# Button_Board.net
KiCad netlist of a schematic drawn in EAGLE
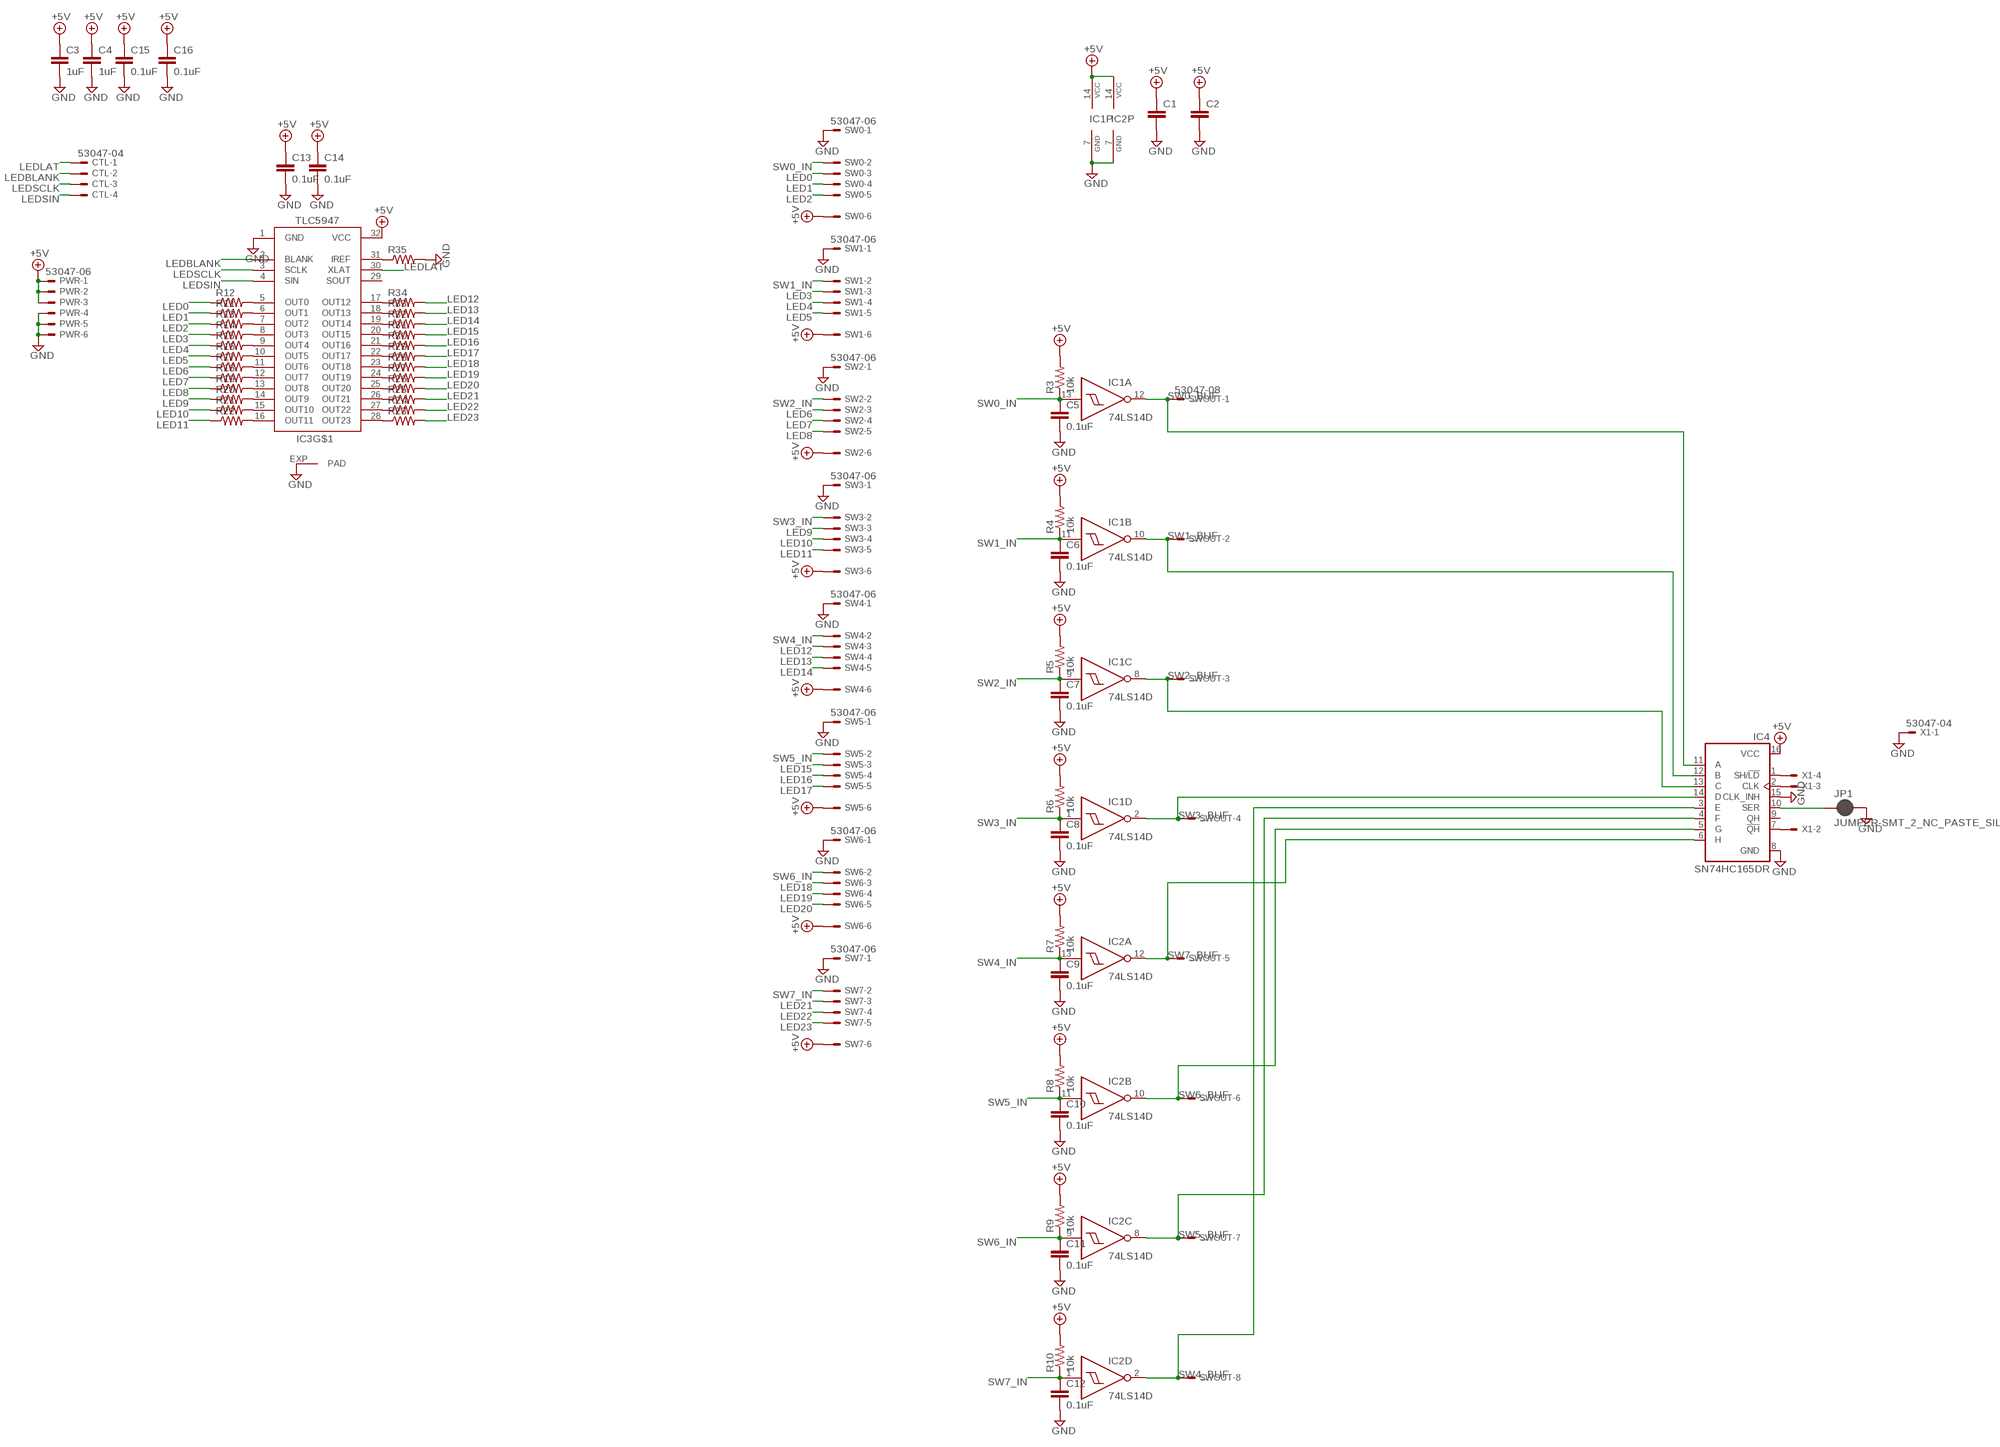
[diagram p0: schematic, sheet 1]

(export (version "E")
  (design (tool "Eeschema 10.0.6"))
  (components
    (comp (ref "C1")
      (value "C-EUC1206")
      (footprint "eagle-import:C1206")
      (libsource (lib "eagle-import") (part "C-EUC1206"))
    )
    (comp (ref "C2")
      (value "C-EUC1206")
      (footprint "eagle-import:C1206")
      (libsource (lib "eagle-import") (part "C-EUC1206"))
    )
    (comp (ref "C3")
      (value "1uF")
      (footprint "eagle-import:C1206K")
      (libsource (lib "eagle-import") (part "C-EUC1206K"))
    )
    (comp (ref "C4")
      (value "1uF")
      (footprint "eagle-import:C1206K")
      (libsource (lib "eagle-import") (part "C-EUC1206K"))
    )
    (comp (ref "C5")
      (value "0.1uF")
      (footprint "eagle-import:C1206")
      (libsource (lib "eagle-import") (part "C-EUC1206"))
    )
    (comp (ref "C6")
      (value "0.1uF")
      (footprint "eagle-import:C1206")
      (libsource (lib "eagle-import") (part "C-EUC1206"))
    )
    (comp (ref "C7")
      (value "0.1uF")
      (footprint "eagle-import:C1206")
      (libsource (lib "eagle-import") (part "C-EUC1206"))
    )
    (comp (ref "C8")
      (value "0.1uF")
      (footprint "eagle-import:C1206")
      (libsource (lib "eagle-import") (part "C-EUC1206"))
    )
    (comp (ref "C9")
      (value "0.1uF")
      (footprint "eagle-import:C1206")
      (libsource (lib "eagle-import") (part "C-EUC1206"))
    )
    (comp (ref "C10")
      (value "0.1uF")
      (footprint "eagle-import:C1206")
      (libsource (lib "eagle-import") (part "C-EUC1206"))
    )
    (comp (ref "C11")
      (value "0.1uF")
      (footprint "eagle-import:C1206")
      (libsource (lib "eagle-import") (part "C-EUC1206"))
    )
    (comp (ref "C12")
      (value "0.1uF")
      (footprint "eagle-import:C1206")
      (libsource (lib "eagle-import") (part "C-EUC1206"))
    )
    (comp (ref "C13")
      (value "0.1uF")
      (footprint "eagle-import:C1206")
      (libsource (lib "eagle-import") (part "C-EUC1206"))
    )
    (comp (ref "C14")
      (value "0.1uF")
      (footprint "eagle-import:C1206")
      (libsource (lib "eagle-import") (part "C-EUC1206"))
    )
    (comp (ref "C15")
      (value "0.1uF")
      (footprint "eagle-import:C1206K")
      (libsource (lib "eagle-import") (part "C-EUC1206K"))
    )
    (comp (ref "C16")
      (value "0.1uF")
      (footprint "eagle-import:C1206K")
      (libsource (lib "eagle-import") (part "C-EUC1206K"))
    )
    (comp (ref "CTL")
      (value "53047-04")
      (footprint "eagle-import:53047-04")
      (fields (field (name "MF") "WALDOM/MOLEX") (field (name "MPN") "53047-0410"))
      (libsource (lib "eagle-import") (part "53?-04047"))
    )
    (comp (ref "IC1")
      (value "74LS14D")
      (footprint "eagle-import:SO14")
      (libsource (lib "eagle-import") (part "7414DLS"))
    )
    (comp (ref "IC2")
      (value "74LS14D")
      (footprint "eagle-import:SO14")
      (libsource (lib "eagle-import") (part "7414DLS"))
    )
    (comp (ref "IC3")
      (value "TLC5947-DAP")
      (footprint "eagle-import:HTSSOP32DAP")
      (libsource (lib "eagle-import") (part "TLC5947-DAP"))
    )
    (comp (ref "IC4")
      (value "SN74HC165DR")
      (footprint "eagle-import:SO16")
      (libsource (lib "eagle-import") (part "74165DHC"))
    )
    (comp (ref "JP1")
      (value "JUMPER-SMT_2_NC_PASTE_SILK")
      (footprint "eagle-import:SMT-JUMPER_2_NC_PASTE_SILK")
      (libsource (lib "eagle-import") (part "JUMPER-SMT_2_NC_PASTE_SILK"))
    )
    (comp (ref "PWR")
      (value "53047-06")
      (footprint "eagle-import:53047-06")
      (fields (field (name "MPN") "53047-0610-C"))
      (libsource (lib "eagle-import") (part "53?-06047"))
    )
    (comp (ref "R3")
      (value "10k")
      (footprint "eagle-import:M1206")
      (libsource (lib "eagle-import") (part "R-US_M1206"))
    )
    (comp (ref "R4")
      (value "10k")
      (footprint "eagle-import:M1206")
      (libsource (lib "eagle-import") (part "R-US_M1206"))
    )
    (comp (ref "R5")
      (value "10k")
      (footprint "eagle-import:M1206")
      (libsource (lib "eagle-import") (part "R-US_M1206"))
    )
    (comp (ref "R6")
      (value "10k")
      (footprint "eagle-import:M1206")
      (libsource (lib "eagle-import") (part "R-US_M1206"))
    )
    (comp (ref "R7")
      (value "10k")
      (footprint "eagle-import:M1206")
      (libsource (lib "eagle-import") (part "R-US_M1206"))
    )
    (comp (ref "R8")
      (value "10k")
      (footprint "eagle-import:M1206")
      (libsource (lib "eagle-import") (part "R-US_M1206"))
    )
    (comp (ref "R9")
      (value "10k")
      (footprint "eagle-import:M1206")
      (libsource (lib "eagle-import") (part "R-US_M1206"))
    )
    (comp (ref "R10")
      (value "10k")
      (footprint "eagle-import:M1206")
      (libsource (lib "eagle-import") (part "R-US_M1206"))
    )
    (comp (ref "R11")
      (value "R-US_M1206")
      (footprint "eagle-import:M1206")
      (libsource (lib "eagle-import") (part "R-US_M1206"))
    )
    (comp (ref "R12")
      (value "R-US_M1206")
      (footprint "eagle-import:M1206")
      (libsource (lib "eagle-import") (part "R-US_M1206"))
    )
    (comp (ref "R13")
      (value "R-US_M1206")
      (footprint "eagle-import:M1206")
      (libsource (lib "eagle-import") (part "R-US_M1206"))
    )
    (comp (ref "R14")
      (value "R-US_M1206")
      (footprint "eagle-import:M1206")
      (libsource (lib "eagle-import") (part "R-US_M1206"))
    )
    (comp (ref "R15")
      (value "R-US_M1206")
      (footprint "eagle-import:M1206")
      (libsource (lib "eagle-import") (part "R-US_M1206"))
    )
    (comp (ref "R16")
      (value "R-US_M1206")
      (footprint "eagle-import:M1206")
      (libsource (lib "eagle-import") (part "R-US_M1206"))
    )
    (comp (ref "R17")
      (value "R-US_M1206")
      (footprint "eagle-import:M1206")
      (libsource (lib "eagle-import") (part "R-US_M1206"))
    )
    (comp (ref "R18")
      (value "R-US_M1206")
      (footprint "eagle-import:M1206")
      (libsource (lib "eagle-import") (part "R-US_M1206"))
    )
    (comp (ref "R19")
      (value "R-US_M1206")
      (footprint "eagle-import:M1206")
      (libsource (lib "eagle-import") (part "R-US_M1206"))
    )
    (comp (ref "R20")
      (value "R-US_M1206")
      (footprint "eagle-import:M1206")
      (libsource (lib "eagle-import") (part "R-US_M1206"))
    )
    (comp (ref "R21")
      (value "R-US_M1206")
      (footprint "eagle-import:M1206")
      (libsource (lib "eagle-import") (part "R-US_M1206"))
    )
    (comp (ref "R22")
      (value "R-US_M1206")
      (footprint "eagle-import:M1206")
      (libsource (lib "eagle-import") (part "R-US_M1206"))
    )
    (comp (ref "R23")
      (value "R-US_M1206")
      (footprint "eagle-import:M1206")
      (libsource (lib "eagle-import") (part "R-US_M1206"))
    )
    (comp (ref "R24")
      (value "R-US_M1206")
      (footprint "eagle-import:M1206")
      (libsource (lib "eagle-import") (part "R-US_M1206"))
    )
    (comp (ref "R25")
      (value "R-US_M1206")
      (footprint "eagle-import:M1206")
      (libsource (lib "eagle-import") (part "R-US_M1206"))
    )
    (comp (ref "R26")
      (value "R-US_M1206")
      (footprint "eagle-import:M1206")
      (libsource (lib "eagle-import") (part "R-US_M1206"))
    )
    (comp (ref "R27")
      (value "R-US_M1206")
      (footprint "eagle-import:M1206")
      (libsource (lib "eagle-import") (part "R-US_M1206"))
    )
    (comp (ref "R28")
      (value "R-US_M1206")
      (footprint "eagle-import:M1206")
      (libsource (lib "eagle-import") (part "R-US_M1206"))
    )
    (comp (ref "R29")
      (value "R-US_M1206")
      (footprint "eagle-import:M1206")
      (libsource (lib "eagle-import") (part "R-US_M1206"))
    )
    (comp (ref "R30")
      (value "R-US_M1206")
      (footprint "eagle-import:M1206")
      (libsource (lib "eagle-import") (part "R-US_M1206"))
    )
    (comp (ref "R31")
      (value "R-US_M1206")
      (footprint "eagle-import:M1206")
      (libsource (lib "eagle-import") (part "R-US_M1206"))
    )
    (comp (ref "R32")
      (value "R-US_M1206")
      (footprint "eagle-import:M1206")
      (libsource (lib "eagle-import") (part "R-US_M1206"))
    )
    (comp (ref "R33")
      (value "R-US_M1206")
      (footprint "eagle-import:M1206")
      (libsource (lib "eagle-import") (part "R-US_M1206"))
    )
    (comp (ref "R34")
      (value "R-US_M1206")
      (footprint "eagle-import:M1206")
      (libsource (lib "eagle-import") (part "R-US_M1206"))
    )
    (comp (ref "R35")
      (value "R-US_M1206")
      (footprint "eagle-import:M1206")
      (libsource (lib "eagle-import") (part "R-US_M1206"))
    )
    (comp (ref "SW0")
      (value "53047-06")
      (footprint "eagle-import:53047-06")
      (fields (field (name "MPN") "53047-0610-C"))
      (libsource (lib "eagle-import") (part "53?-06047"))
    )
    (comp (ref "SW1")
      (value "53047-06")
      (footprint "eagle-import:53047-06")
      (fields (field (name "MPN") "53047-0610-C"))
      (libsource (lib "eagle-import") (part "53?-06047"))
    )
    (comp (ref "SW2")
      (value "53047-06")
      (footprint "eagle-import:53047-06")
      (fields (field (name "MPN") "53047-0610-C"))
      (libsource (lib "eagle-import") (part "53?-06047"))
    )
    (comp (ref "SW3")
      (value "53047-06")
      (footprint "eagle-import:53047-06")
      (fields (field (name "MPN") "53047-0610-C"))
      (libsource (lib "eagle-import") (part "53?-06047"))
    )
    (comp (ref "SW4")
      (value "53047-06")
      (footprint "eagle-import:53047-06")
      (fields (field (name "MPN") "53047-0610-C"))
      (libsource (lib "eagle-import") (part "53?-06047"))
    )
    (comp (ref "SW5")
      (value "53047-06")
      (footprint "eagle-import:53047-06")
      (fields (field (name "MPN") "53047-0610-C"))
      (libsource (lib "eagle-import") (part "53?-06047"))
    )
    (comp (ref "SW6")
      (value "53047-06")
      (footprint "eagle-import:53047-06")
      (fields (field (name "MPN") "53047-0610-C"))
      (libsource (lib "eagle-import") (part "53?-06047"))
    )
    (comp (ref "SW7")
      (value "53047-06")
      (footprint "eagle-import:53047-06")
      (fields (field (name "MPN") "53047-0610-C"))
      (libsource (lib "eagle-import") (part "53?-06047"))
    )
    (comp (ref "SWOUT")
      (value "53047-08")
      (footprint "eagle-import:53047-08")
      (fields (field (name "MPN") "53047-0810"))
      (libsource (lib "eagle-import") (part "53?-08047"))
    )
    (comp (ref "X1")
      (value "53047-04")
      (footprint "eagle-import:53047-04")
      (fields (field (name "MF") "WALDOM/MOLEX") (field (name "MPN") "53047-0410"))
      (libsource (lib "eagle-import") (part "53?-04047"))
    )
  )
  (nets
    (net (code "1") (name "+5V") (class "Default")
      (node (ref "C1") (pin "1") (pinfunction "1_1") (pintype "passive"))
      (node (ref "C13") (pin "1") (pinfunction "1_1") (pintype "passive"))
      (node (ref "C14") (pin "1") (pinfunction "1_1") (pintype "passive"))
      (node (ref "C15") (pin "1") (pinfunction "1_1") (pintype "passive"))
      (node (ref "C16") (pin "1") (pinfunction "1_1") (pintype "passive"))
      (node (ref "C2") (pin "1") (pinfunction "1_1") (pintype "passive"))
      (node (ref "C3") (pin "1") (pinfunction "1_1") (pintype "passive"))
      (node (ref "C4") (pin "1") (pinfunction "1_1") (pintype "passive"))
      (node (ref "IC1") (pin "14") (pinfunction "VCC_14") (pintype "power_in"))
      (node (ref "IC2") (pin "14") (pinfunction "VCC_14") (pintype "power_in"))
      (node (ref "IC3") (pin "32") (pinfunction "VCC_32") (pintype "power_in"))
      (node (ref "IC4") (pin "16") (pinfunction "VCC_16") (pintype "power_in"))
      (node (ref "PWR") (pin "1") (pinfunction "S_1") (pintype "passive"))
      (node (ref "PWR") (pin "2") (pinfunction "S_2") (pintype "passive"))
      (node (ref "PWR") (pin "3") (pinfunction "S_3") (pintype "passive"))
      (node (ref "R10") (pin "2") (pinfunction "2_2") (pintype "passive"))
      (node (ref "R3") (pin "2") (pinfunction "2_2") (pintype "passive"))
      (node (ref "R4") (pin "2") (pinfunction "2_2") (pintype "passive"))
      (node (ref "R5") (pin "2") (pinfunction "2_2") (pintype "passive"))
      (node (ref "R6") (pin "2") (pinfunction "2_2") (pintype "passive"))
      (node (ref "R7") (pin "2") (pinfunction "2_2") (pintype "passive"))
      (node (ref "R8") (pin "2") (pinfunction "2_2") (pintype "passive"))
      (node (ref "R9") (pin "2") (pinfunction "2_2") (pintype "passive"))
      (node (ref "SW0") (pin "6") (pinfunction "S_6") (pintype "passive"))
      (node (ref "SW1") (pin "6") (pinfunction "S_6") (pintype "passive"))
      (node (ref "SW2") (pin "6") (pinfunction "S_6") (pintype "passive"))
      (node (ref "SW3") (pin "6") (pinfunction "S_6") (pintype "passive"))
      (node (ref "SW4") (pin "6") (pinfunction "S_6") (pintype "passive"))
      (node (ref "SW5") (pin "6") (pinfunction "S_6") (pintype "passive"))
      (node (ref "SW6") (pin "6") (pinfunction "S_6") (pintype "passive"))
      (node (ref "SW7") (pin "6") (pinfunction "S_6") (pintype "passive"))
    )
    (net (code "2") (name "/LED0") (class "Default")
      (node (ref "R12") (pin "1") (pinfunction "1_1") (pintype "passive"))
      (node (ref "SW0") (pin "3") (pinfunction "S_3") (pintype "passive"))
    )
    (net (code "3") (name "/LED1") (class "Default")
      (node (ref "R11") (pin "1") (pinfunction "1_1") (pintype "passive"))
      (node (ref "SW0") (pin "4") (pinfunction "S_4") (pintype "passive"))
    )
    (net (code "4") (name "/LED2") (class "Default")
      (node (ref "R13") (pin "1") (pinfunction "1_1") (pintype "passive"))
      (node (ref "SW0") (pin "5") (pinfunction "S_5") (pintype "passive"))
    )
    (net (code "5") (name "/LED3") (class "Default")
      (node (ref "R14") (pin "1") (pinfunction "1_1") (pintype "passive"))
      (node (ref "SW1") (pin "3") (pinfunction "S_3") (pintype "passive"))
    )
    (net (code "6") (name "/LED4") (class "Default")
      (node (ref "R15") (pin "1") (pinfunction "1_1") (pintype "passive"))
      (node (ref "SW1") (pin "4") (pinfunction "S_4") (pintype "passive"))
    )
    (net (code "7") (name "/LED5") (class "Default")
      (node (ref "R16") (pin "1") (pinfunction "1_1") (pintype "passive"))
      (node (ref "SW1") (pin "5") (pinfunction "S_5") (pintype "passive"))
    )
    (net (code "8") (name "/LED6") (class "Default")
      (node (ref "R17") (pin "1") (pinfunction "1_1") (pintype "passive"))
      (node (ref "SW2") (pin "3") (pinfunction "S_3") (pintype "passive"))
    )
    (net (code "9") (name "/LED7") (class "Default")
      (node (ref "R18") (pin "1") (pinfunction "1_1") (pintype "passive"))
      (node (ref "SW2") (pin "4") (pinfunction "S_4") (pintype "passive"))
    )
    (net (code "10") (name "/LED8") (class "Default")
      (node (ref "R19") (pin "1") (pinfunction "1_1") (pintype "passive"))
      (node (ref "SW2") (pin "5") (pinfunction "S_5") (pintype "passive"))
    )
    (net (code "11") (name "/LED9") (class "Default")
      (node (ref "R20") (pin "1") (pinfunction "1_1") (pintype "passive"))
      (node (ref "SW3") (pin "3") (pinfunction "S_3") (pintype "passive"))
    )
    (net (code "12") (name "/LED10") (class "Default")
      (node (ref "R21") (pin "1") (pinfunction "1_1") (pintype "passive"))
      (node (ref "SW3") (pin "4") (pinfunction "S_4") (pintype "passive"))
    )
    (net (code "13") (name "/LED11") (class "Default")
      (node (ref "R22") (pin "1") (pinfunction "1_1") (pintype "passive"))
      (node (ref "SW3") (pin "5") (pinfunction "S_5") (pintype "passive"))
    )
    (net (code "14") (name "/LED12") (class "Default")
      (node (ref "R34") (pin "2") (pinfunction "2_2") (pintype "passive"))
      (node (ref "SW4") (pin "3") (pinfunction "S_3") (pintype "passive"))
    )
    (net (code "15") (name "/LED13") (class "Default")
      (node (ref "R33") (pin "2") (pinfunction "2_2") (pintype "passive"))
      (node (ref "SW4") (pin "4") (pinfunction "S_4") (pintype "passive"))
    )
    (net (code "16") (name "/LED14") (class "Default")
      (node (ref "R32") (pin "2") (pinfunction "2_2") (pintype "passive"))
      (node (ref "SW4") (pin "5") (pinfunction "S_5") (pintype "passive"))
    )
    (net (code "17") (name "/LED15") (class "Default")
      (node (ref "R31") (pin "2") (pinfunction "2_2") (pintype "passive"))
      (node (ref "SW5") (pin "3") (pinfunction "S_3") (pintype "passive"))
    )
    (net (code "18") (name "/LED16") (class "Default")
      (node (ref "R30") (pin "2") (pinfunction "2_2") (pintype "passive"))
      (node (ref "SW5") (pin "4") (pinfunction "S_4") (pintype "passive"))
    )
    (net (code "19") (name "/LED17") (class "Default")
      (node (ref "R29") (pin "2") (pinfunction "2_2") (pintype "passive"))
      (node (ref "SW5") (pin "5") (pinfunction "S_5") (pintype "passive"))
    )
    (net (code "20") (name "/LED18") (class "Default")
      (node (ref "R28") (pin "2") (pinfunction "2_2") (pintype "passive"))
      (node (ref "SW6") (pin "3") (pinfunction "S_3") (pintype "passive"))
    )
    (net (code "21") (name "/LED19") (class "Default")
      (node (ref "R27") (pin "2") (pinfunction "2_2") (pintype "passive"))
      (node (ref "SW6") (pin "4") (pinfunction "S_4") (pintype "passive"))
    )
    (net (code "22") (name "/LED20") (class "Default")
      (node (ref "R26") (pin "2") (pinfunction "2_2") (pintype "passive"))
      (node (ref "SW6") (pin "5") (pinfunction "S_5") (pintype "passive"))
    )
    (net (code "23") (name "/LED21") (class "Default")
      (node (ref "R25") (pin "2") (pinfunction "2_2") (pintype "passive"))
      (node (ref "SW7") (pin "3") (pinfunction "S_3") (pintype "passive"))
    )
    (net (code "24") (name "/LED22") (class "Default")
      (node (ref "R24") (pin "2") (pinfunction "2_2") (pintype "passive"))
      (node (ref "SW7") (pin "4") (pinfunction "S_4") (pintype "passive"))
    )
    (net (code "25") (name "/LED23") (class "Default")
      (node (ref "R23") (pin "2") (pinfunction "2_2") (pintype "passive"))
      (node (ref "SW7") (pin "5") (pinfunction "S_5") (pintype "passive"))
    )
    (net (code "26") (name "/LEDBLANK") (class "Default")
      (node (ref "CTL") (pin "2") (pinfunction "S_2") (pintype "passive"))
      (node (ref "IC3") (pin "2") (pinfunction "BLANK_2") (pintype "input"))
    )
    (net (code "27") (name "/LEDLAT") (class "Default")
      (node (ref "CTL") (pin "1") (pinfunction "S_1") (pintype "passive"))
      (node (ref "IC3") (pin "30") (pinfunction "XLAT_30") (pintype "input"))
    )
    (net (code "28") (name "/LEDSCLK") (class "Default")
      (node (ref "CTL") (pin "3") (pinfunction "S_3") (pintype "passive"))
      (node (ref "IC3") (pin "3") (pinfunction "SCLK_3") (pintype "input"))
    )
    (net (code "29") (name "/LEDSIN") (class "Default")
      (node (ref "CTL") (pin "4") (pinfunction "S_4") (pintype "passive"))
      (node (ref "IC3") (pin "4") (pinfunction "SIN_4") (pintype "input"))
    )
    (net (code "30") (name "/SW0_BUF") (class "Default")
      (node (ref "IC1") (pin "12") (pinfunction "O_12") (pintype "output"))
      (node (ref "IC4") (pin "11") (pinfunction "A_11") (pintype "tri_state"))
      (node (ref "SWOUT") (pin "1") (pinfunction "S_1") (pintype "passive"))
    )
    (net (code "31") (name "/SW0_IN") (class "Default")
      (node (ref "C5") (pin "1") (pinfunction "1_1") (pintype "passive"))
      (node (ref "IC1") (pin "13") (pinfunction "I_13") (pintype "input"))
      (node (ref "R3") (pin "1") (pinfunction "1_1") (pintype "passive"))
      (node (ref "SW0") (pin "2") (pinfunction "S_2") (pintype "passive"))
    )
    (net (code "32") (name "/SW1_BUF") (class "Default")
      (node (ref "IC1") (pin "10") (pinfunction "O_10") (pintype "output"))
      (node (ref "IC4") (pin "12") (pinfunction "B_12") (pintype "tri_state"))
      (node (ref "SWOUT") (pin "2") (pinfunction "S_2") (pintype "passive"))
    )
    (net (code "33") (name "/SW1_IN") (class "Default")
      (node (ref "C6") (pin "1") (pinfunction "1_1") (pintype "passive"))
      (node (ref "IC1") (pin "11") (pinfunction "I_11") (pintype "input"))
      (node (ref "R4") (pin "1") (pinfunction "1_1") (pintype "passive"))
      (node (ref "SW1") (pin "2") (pinfunction "S_2") (pintype "passive"))
    )
    (net (code "34") (name "/SW2_BUF") (class "Default")
      (node (ref "IC1") (pin "8") (pinfunction "O_8") (pintype "output"))
      (node (ref "IC4") (pin "13") (pinfunction "C_13") (pintype "tri_state"))
      (node (ref "SWOUT") (pin "3") (pinfunction "S_3") (pintype "passive"))
    )
    (net (code "35") (name "/SW2_IN") (class "Default")
      (node (ref "C7") (pin "1") (pinfunction "1_1") (pintype "passive"))
      (node (ref "IC1") (pin "9") (pinfunction "I_9") (pintype "input"))
      (node (ref "R5") (pin "1") (pinfunction "1_1") (pintype "passive"))
      (node (ref "SW2") (pin "2") (pinfunction "S_2") (pintype "passive"))
    )
    (net (code "36") (name "/SW3_BUF") (class "Default")
      (node (ref "IC1") (pin "2") (pinfunction "O_2") (pintype "output"))
      (node (ref "IC4") (pin "14") (pinfunction "D_14") (pintype "tri_state"))
      (node (ref "SWOUT") (pin "4") (pinfunction "S_4") (pintype "passive"))
    )
    (net (code "37") (name "/SW3_IN") (class "Default")
      (node (ref "C8") (pin "1") (pinfunction "1_1") (pintype "passive"))
      (node (ref "IC1") (pin "1") (pinfunction "I_1") (pintype "input"))
      (node (ref "R6") (pin "1") (pinfunction "1_1") (pintype "passive"))
      (node (ref "SW3") (pin "2") (pinfunction "S_2") (pintype "passive"))
    )
    (net (code "38") (name "/SW4_BUF") (class "Default")
      (node (ref "IC2") (pin "2") (pinfunction "O_2") (pintype "output"))
      (node (ref "IC4") (pin "3") (pinfunction "E_3") (pintype "tri_state"))
      (node (ref "SWOUT") (pin "8") (pinfunction "S_8") (pintype "passive"))
    )
    (net (code "39") (name "/SW4_IN") (class "Default")
      (node (ref "C9") (pin "1") (pinfunction "1_1") (pintype "passive"))
      (node (ref "IC2") (pin "13") (pinfunction "I_13") (pintype "input"))
      (node (ref "R7") (pin "1") (pinfunction "1_1") (pintype "passive"))
      (node (ref "SW4") (pin "2") (pinfunction "S_2") (pintype "passive"))
    )
    (net (code "40") (name "/SW5_BUF") (class "Default")
      (node (ref "IC2") (pin "8") (pinfunction "O_8") (pintype "output"))
      (node (ref "IC4") (pin "4") (pinfunction "F_4") (pintype "tri_state"))
      (node (ref "SWOUT") (pin "7") (pinfunction "S_7") (pintype "passive"))
    )
    (net (code "41") (name "/SW5_IN") (class "Default")
      (node (ref "C10") (pin "1") (pinfunction "1_1") (pintype "passive"))
      (node (ref "IC2") (pin "11") (pinfunction "I_11") (pintype "input"))
      (node (ref "R8") (pin "1") (pinfunction "1_1") (pintype "passive"))
      (node (ref "SW5") (pin "2") (pinfunction "S_2") (pintype "passive"))
    )
    (net (code "42") (name "/SW6_BUF") (class "Default")
      (node (ref "IC2") (pin "10") (pinfunction "O_10") (pintype "output"))
      (node (ref "IC4") (pin "5") (pinfunction "G_5") (pintype "tri_state"))
      (node (ref "SWOUT") (pin "6") (pinfunction "S_6") (pintype "passive"))
    )
    (net (code "43") (name "/SW6_IN") (class "Default")
      (node (ref "C11") (pin "1") (pinfunction "1_1") (pintype "passive"))
      (node (ref "IC2") (pin "9") (pinfunction "I_9") (pintype "input"))
      (node (ref "R9") (pin "1") (pinfunction "1_1") (pintype "passive"))
      (node (ref "SW6") (pin "2") (pinfunction "S_2") (pintype "passive"))
    )
    (net (code "44") (name "/SW7_BUF") (class "Default")
      (node (ref "IC2") (pin "12") (pinfunction "O_12") (pintype "output"))
      (node (ref "IC4") (pin "6") (pinfunction "H_6") (pintype "tri_state"))
      (node (ref "SWOUT") (pin "5") (pinfunction "S_5") (pintype "passive"))
    )
    (net (code "45") (name "/SW7_IN") (class "Default")
      (node (ref "C12") (pin "1") (pinfunction "1_1") (pintype "passive"))
      (node (ref "IC2") (pin "1") (pinfunction "I_1") (pintype "input"))
      (node (ref "R10") (pin "1") (pinfunction "1_1") (pintype "passive"))
      (node (ref "SW7") (pin "2") (pinfunction "S_2") (pintype "passive"))
    )
    (net (code "46") (name "GND") (class "Default")
      (node (ref "C1") (pin "2") (pinfunction "2_2") (pintype "passive"))
      (node (ref "C10") (pin "2") (pinfunction "2_2") (pintype "passive"))
      (node (ref "C11") (pin "2") (pinfunction "2_2") (pintype "passive"))
      (node (ref "C12") (pin "2") (pinfunction "2_2") (pintype "passive"))
      (node (ref "C13") (pin "2") (pinfunction "2_2") (pintype "passive"))
      (node (ref "C14") (pin "2") (pinfunction "2_2") (pintype "passive"))
      (node (ref "C15") (pin "2") (pinfunction "2_2") (pintype "passive"))
      (node (ref "C16") (pin "2") (pinfunction "2_2") (pintype "passive"))
      (node (ref "C2") (pin "2") (pinfunction "2_2") (pintype "passive"))
      (node (ref "C3") (pin "2") (pinfunction "2_2") (pintype "passive"))
      (node (ref "C4") (pin "2") (pinfunction "2_2") (pintype "passive"))
      (node (ref "C5") (pin "2") (pinfunction "2_2") (pintype "passive"))
      (node (ref "C6") (pin "2") (pinfunction "2_2") (pintype "passive"))
      (node (ref "C7") (pin "2") (pinfunction "2_2") (pintype "passive"))
      (node (ref "C8") (pin "2") (pinfunction "2_2") (pintype "passive"))
      (node (ref "C9") (pin "2") (pinfunction "2_2") (pintype "passive"))
      (node (ref "IC1") (pin "7") (pinfunction "GND_7") (pintype "power_in"))
      (node (ref "IC2") (pin "7") (pinfunction "GND_7") (pintype "power_in"))
      (node (ref "IC3") (pin "1") (pinfunction "GND_1") (pintype "power_in"))
      (node (ref "IC3") (pin "EXP") (pinfunction "PAD_EXP") (pintype "passive"))
      (node (ref "IC4") (pin "15") (pinfunction "CLK_INH_15") (pintype "input"))
      (node (ref "IC4") (pin "8") (pinfunction "GND_8") (pintype "power_in"))
      (node (ref "JP1") (pin "2") (pinfunction "2_2") (pintype "passive"))
      (node (ref "PWR") (pin "4") (pinfunction "S_4") (pintype "passive"))
      (node (ref "PWR") (pin "5") (pinfunction "S_5") (pintype "passive"))
      (node (ref "PWR") (pin "6") (pinfunction "S_6") (pintype "passive"))
      (node (ref "R35") (pin "2") (pinfunction "2_2") (pintype "passive"))
      (node (ref "SW0") (pin "1") (pinfunction "S_1") (pintype "passive"))
      (node (ref "SW1") (pin "1") (pinfunction "S_1") (pintype "passive"))
      (node (ref "SW2") (pin "1") (pinfunction "S_1") (pintype "passive"))
      (node (ref "SW3") (pin "1") (pinfunction "S_1") (pintype "passive"))
      (node (ref "SW4") (pin "1") (pinfunction "S_1") (pintype "passive"))
      (node (ref "SW5") (pin "1") (pinfunction "S_1") (pintype "passive"))
      (node (ref "SW6") (pin "1") (pinfunction "S_1") (pintype "passive"))
      (node (ref "SW7") (pin "1") (pinfunction "S_1") (pintype "passive"))
      (node (ref "X1") (pin "1") (pinfunction "S_1") (pintype "passive"))
    )
    (net (code "47") (name "Net-(IC3A-IREF)") (class "Default")
      (node (ref "IC3") (pin "31") (pinfunction "IREF_31") (pintype "bidirectional"))
      (node (ref "R35") (pin "1") (pinfunction "1_1") (pintype "passive"))
    )
    (net (code "48") (name "Net-(IC3A-OUT0)") (class "Default")
      (node (ref "IC3") (pin "5") (pinfunction "OUT0_5") (pintype "open_collector"))
      (node (ref "R12") (pin "2") (pinfunction "2_2") (pintype "passive"))
    )
    (net (code "49") (name "Net-(IC3A-OUT1)") (class "Default")
      (node (ref "IC3") (pin "6") (pinfunction "OUT1_6") (pintype "open_collector"))
      (node (ref "R11") (pin "2") (pinfunction "2_2") (pintype "passive"))
    )
    (net (code "50") (name "Net-(IC3A-OUT2)") (class "Default")
      (node (ref "IC3") (pin "7") (pinfunction "OUT2_7") (pintype "open_collector"))
      (node (ref "R13") (pin "2") (pinfunction "2_2") (pintype "passive"))
    )
    (net (code "51") (name "Net-(IC3A-OUT3)") (class "Default")
      (node (ref "IC3") (pin "8") (pinfunction "OUT3_8") (pintype "open_collector"))
      (node (ref "R14") (pin "2") (pinfunction "2_2") (pintype "passive"))
    )
    (net (code "52") (name "Net-(IC3A-OUT4)") (class "Default")
      (node (ref "IC3") (pin "9") (pinfunction "OUT4_9") (pintype "open_collector"))
      (node (ref "R15") (pin "2") (pinfunction "2_2") (pintype "passive"))
    )
    (net (code "53") (name "Net-(IC3A-OUT5)") (class "Default")
      (node (ref "IC3") (pin "10") (pinfunction "OUT5_10") (pintype "open_collector"))
      (node (ref "R16") (pin "2") (pinfunction "2_2") (pintype "passive"))
    )
    (net (code "54") (name "Net-(IC3A-OUT6)") (class "Default")
      (node (ref "IC3") (pin "11") (pinfunction "OUT6_11") (pintype "open_collector"))
      (node (ref "R17") (pin "2") (pinfunction "2_2") (pintype "passive"))
    )
    (net (code "55") (name "Net-(IC3A-OUT7)") (class "Default")
      (node (ref "IC3") (pin "12") (pinfunction "OUT7_12") (pintype "open_collector"))
      (node (ref "R18") (pin "2") (pinfunction "2_2") (pintype "passive"))
    )
    (net (code "56") (name "Net-(IC3A-OUT8)") (class "Default")
      (node (ref "IC3") (pin "13") (pinfunction "OUT8_13") (pintype "open_collector"))
      (node (ref "R19") (pin "2") (pinfunction "2_2") (pintype "passive"))
    )
    (net (code "57") (name "Net-(IC3A-OUT9)") (class "Default")
      (node (ref "IC3") (pin "14") (pinfunction "OUT9_14") (pintype "open_collector"))
      (node (ref "R20") (pin "2") (pinfunction "2_2") (pintype "passive"))
    )
    (net (code "58") (name "Net-(IC3A-OUT10)") (class "Default")
      (node (ref "IC3") (pin "15") (pinfunction "OUT10_15") (pintype "open_collector"))
      (node (ref "R21") (pin "2") (pinfunction "2_2") (pintype "passive"))
    )
    (net (code "59") (name "Net-(IC3A-OUT11)") (class "Default")
      (node (ref "IC3") (pin "16") (pinfunction "OUT11_16") (pintype "open_collector"))
      (node (ref "R22") (pin "2") (pinfunction "2_2") (pintype "passive"))
    )
    (net (code "60") (name "Net-(IC3A-OUT12)") (class "Default")
      (node (ref "IC3") (pin "17") (pinfunction "OUT12_17") (pintype "open_collector"))
      (node (ref "R34") (pin "1") (pinfunction "1_1") (pintype "passive"))
    )
    (net (code "61") (name "Net-(IC3A-OUT13)") (class "Default")
      (node (ref "IC3") (pin "18") (pinfunction "OUT13_18") (pintype "open_collector"))
      (node (ref "R33") (pin "1") (pinfunction "1_1") (pintype "passive"))
    )
    (net (code "62") (name "Net-(IC3A-OUT14)") (class "Default")
      (node (ref "IC3") (pin "19") (pinfunction "OUT14_19") (pintype "open_collector"))
      (node (ref "R32") (pin "1") (pinfunction "1_1") (pintype "passive"))
    )
    (net (code "63") (name "Net-(IC3A-OUT15)") (class "Default")
      (node (ref "IC3") (pin "20") (pinfunction "OUT15_20") (pintype "open_collector"))
      (node (ref "R31") (pin "1") (pinfunction "1_1") (pintype "passive"))
    )
    (net (code "64") (name "Net-(IC3A-OUT16)") (class "Default")
      (node (ref "IC3") (pin "21") (pinfunction "OUT16_21") (pintype "open_collector"))
      (node (ref "R30") (pin "1") (pinfunction "1_1") (pintype "passive"))
    )
    (net (code "65") (name "Net-(IC3A-OUT17)") (class "Default")
      (node (ref "IC3") (pin "22") (pinfunction "OUT17_22") (pintype "open_collector"))
      (node (ref "R29") (pin "1") (pinfunction "1_1") (pintype "passive"))
    )
    (net (code "66") (name "Net-(IC3A-OUT18)") (class "Default")
      (node (ref "IC3") (pin "23") (pinfunction "OUT18_23") (pintype "open_collector"))
      (node (ref "R28") (pin "1") (pinfunction "1_1") (pintype "passive"))
    )
    (net (code "67") (name "Net-(IC3A-OUT19)") (class "Default")
      (node (ref "IC3") (pin "24") (pinfunction "OUT19_24") (pintype "open_collector"))
      (node (ref "R27") (pin "1") (pinfunction "1_1") (pintype "passive"))
    )
    (net (code "68") (name "Net-(IC3A-OUT20)") (class "Default")
      (node (ref "IC3") (pin "25") (pinfunction "OUT20_25") (pintype "open_collector"))
      (node (ref "R26") (pin "1") (pinfunction "1_1") (pintype "passive"))
    )
    (net (code "69") (name "Net-(IC3A-OUT21)") (class "Default")
      (node (ref "IC3") (pin "26") (pinfunction "OUT21_26") (pintype "open_collector"))
      (node (ref "R25") (pin "1") (pinfunction "1_1") (pintype "passive"))
    )
    (net (code "70") (name "Net-(IC3A-OUT22)") (class "Default")
      (node (ref "IC3") (pin "27") (pinfunction "OUT22_27") (pintype "open_collector"))
      (node (ref "R24") (pin "1") (pinfunction "1_1") (pintype "passive"))
    )
    (net (code "71") (name "Net-(IC3A-OUT23)") (class "Default")
      (node (ref "IC3") (pin "28") (pinfunction "OUT23_28") (pintype "open_collector"))
      (node (ref "R23") (pin "1") (pinfunction "1_1") (pintype "passive"))
    )
    (net (code "72") (name "Net-(IC4-CLK)") (class "Default")
      (node (ref "IC4") (pin "2") (pinfunction "CLK_2") (pintype "input"))
      (node (ref "X1") (pin "3") (pinfunction "S_3") (pintype "passive"))
    )
    (net (code "73") (name "Net-(IC4-SER)") (class "Default")
      (node (ref "IC4") (pin "10") (pinfunction "SER_10") (pintype "input"))
      (node (ref "JP1") (pin "1") (pinfunction "1_1") (pintype "passive"))
    )
    (net (code "74") (name "Net-(IC4-SH{slash}~{LD})") (class "Default")
      (node (ref "IC4") (pin "1") (pinfunction "SH/~{LD}_1") (pintype "input"))
      (node (ref "X1") (pin "4") (pinfunction "S_4") (pintype "passive"))
    )
    (net (code "75") (name "Net-(IC4-~{QH})") (class "Default")
      (node (ref "IC4") (pin "7") (pinfunction "~{QH}_7") (pintype "input"))
      (node (ref "X1") (pin "2") (pinfunction "S_2") (pintype "passive"))
    )
    (net (code "76") (name "unconnected-(IC3A-SOUT-Pad29)") (class "Default")
      (node (ref "IC3") (pin "29") (pinfunction "SOUT_29") (pintype "output"))
    )
    (net (code "77") (name "unconnected-(IC4-QH-Pad9)") (class "Default")
      (node (ref "IC4") (pin "9") (pinfunction "QH_9") (pintype "tri_state"))
    )
  )
)
